# EPS_Flatsat_Module.net
KiCad netlist of a schematic drawn in EAGLE
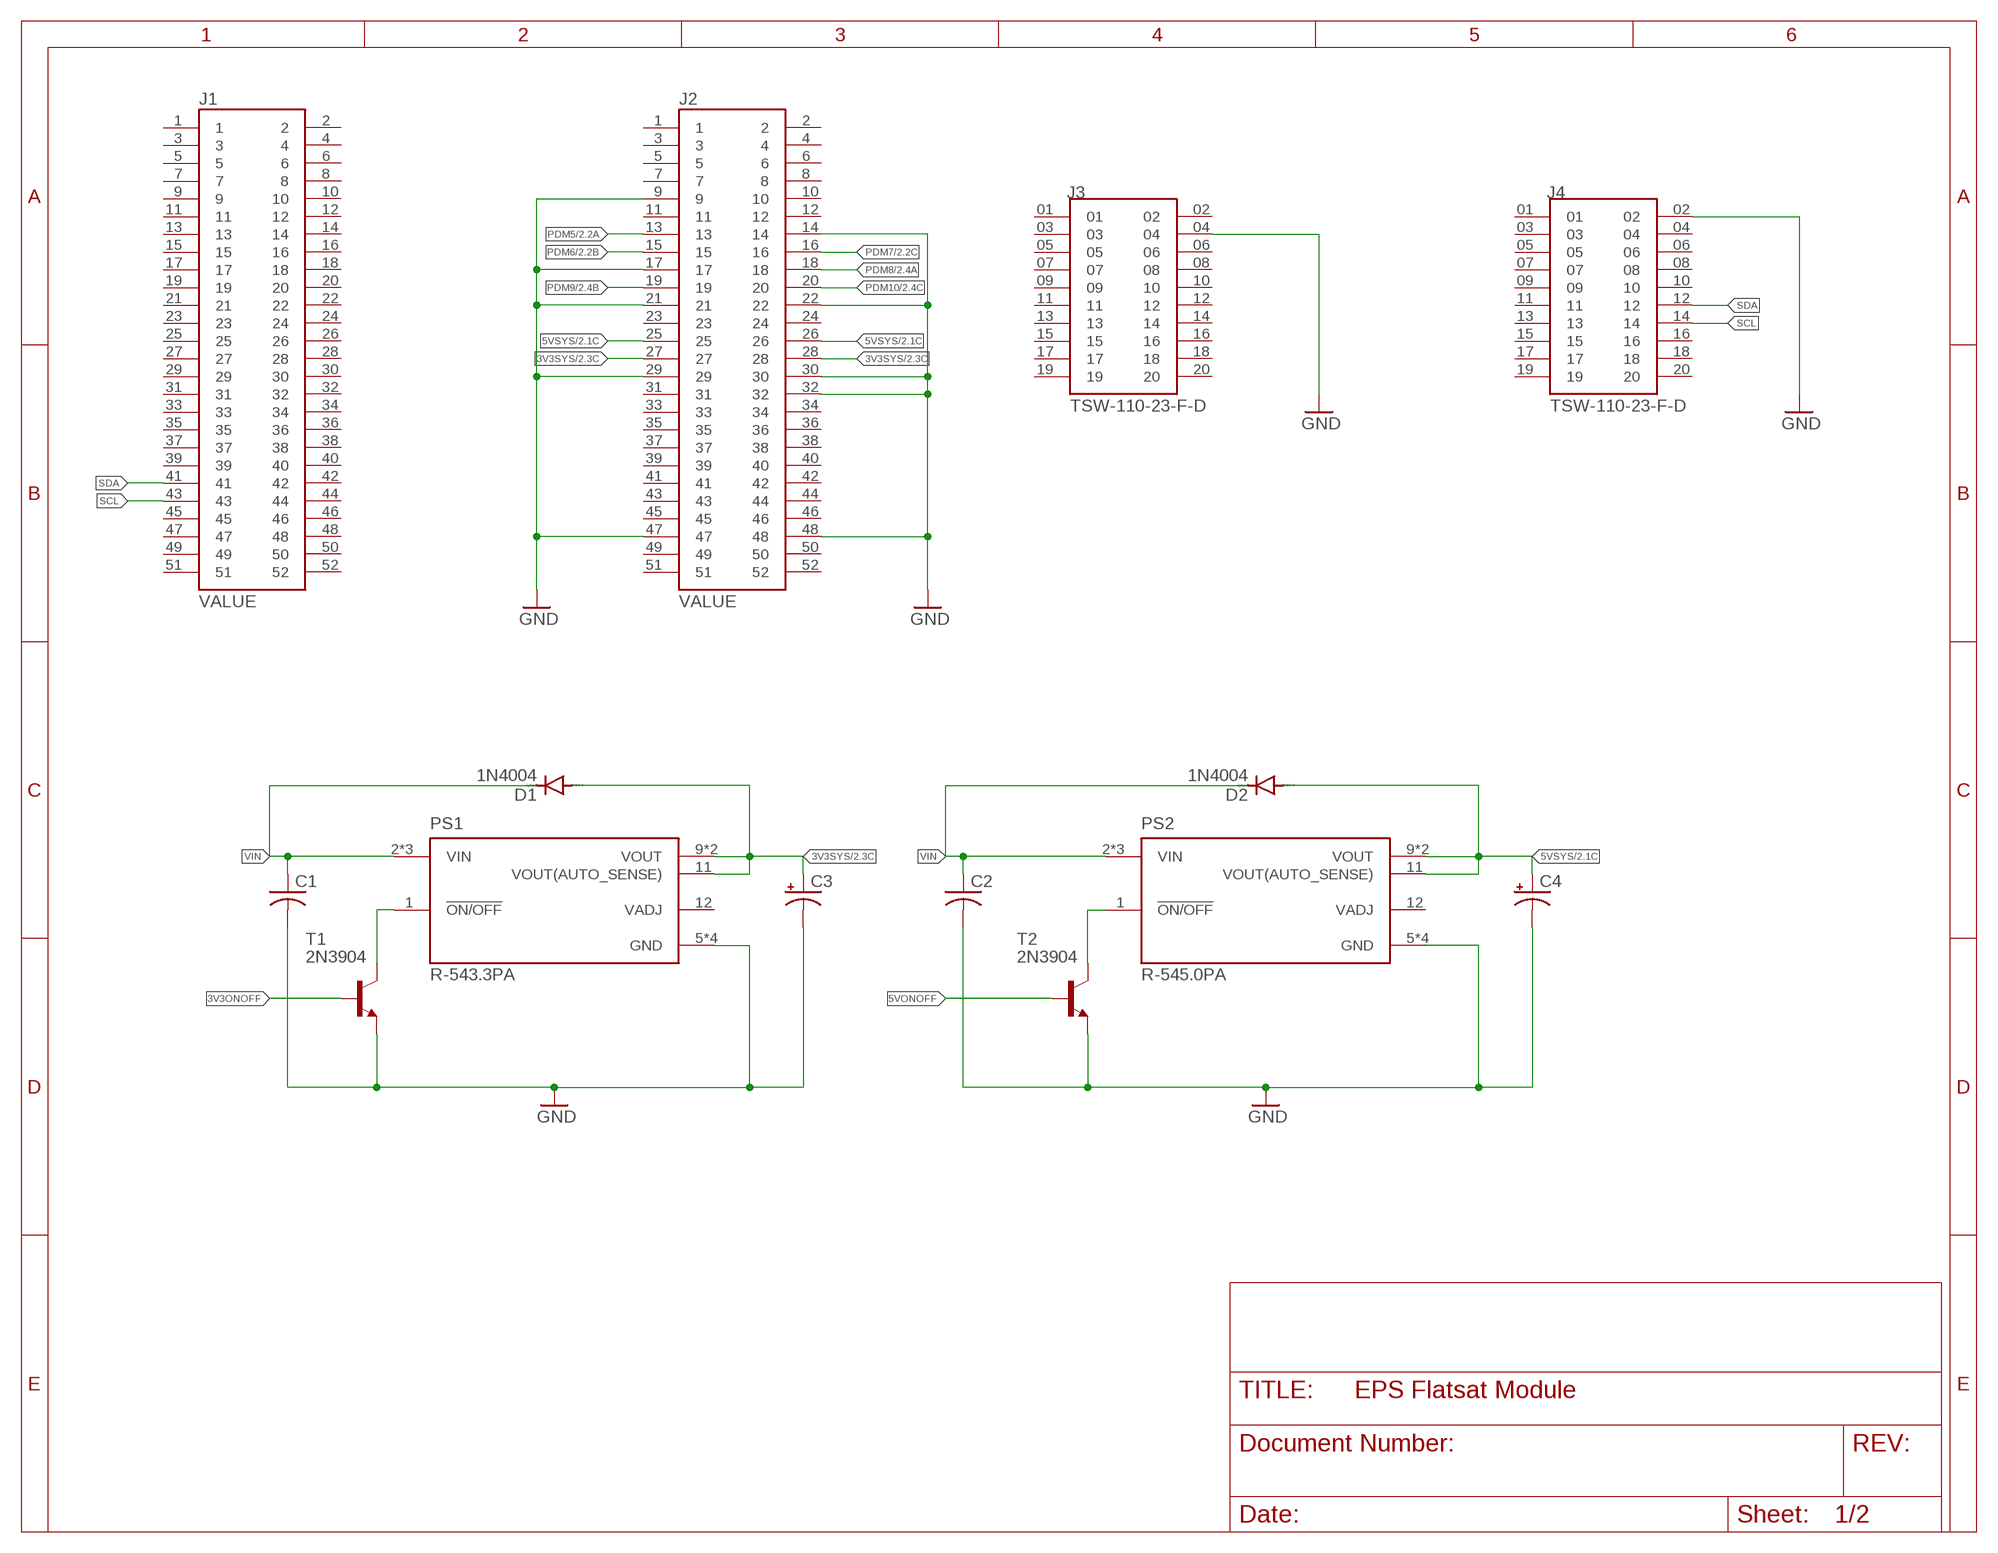
[diagram p0: schematic, sheet 1]
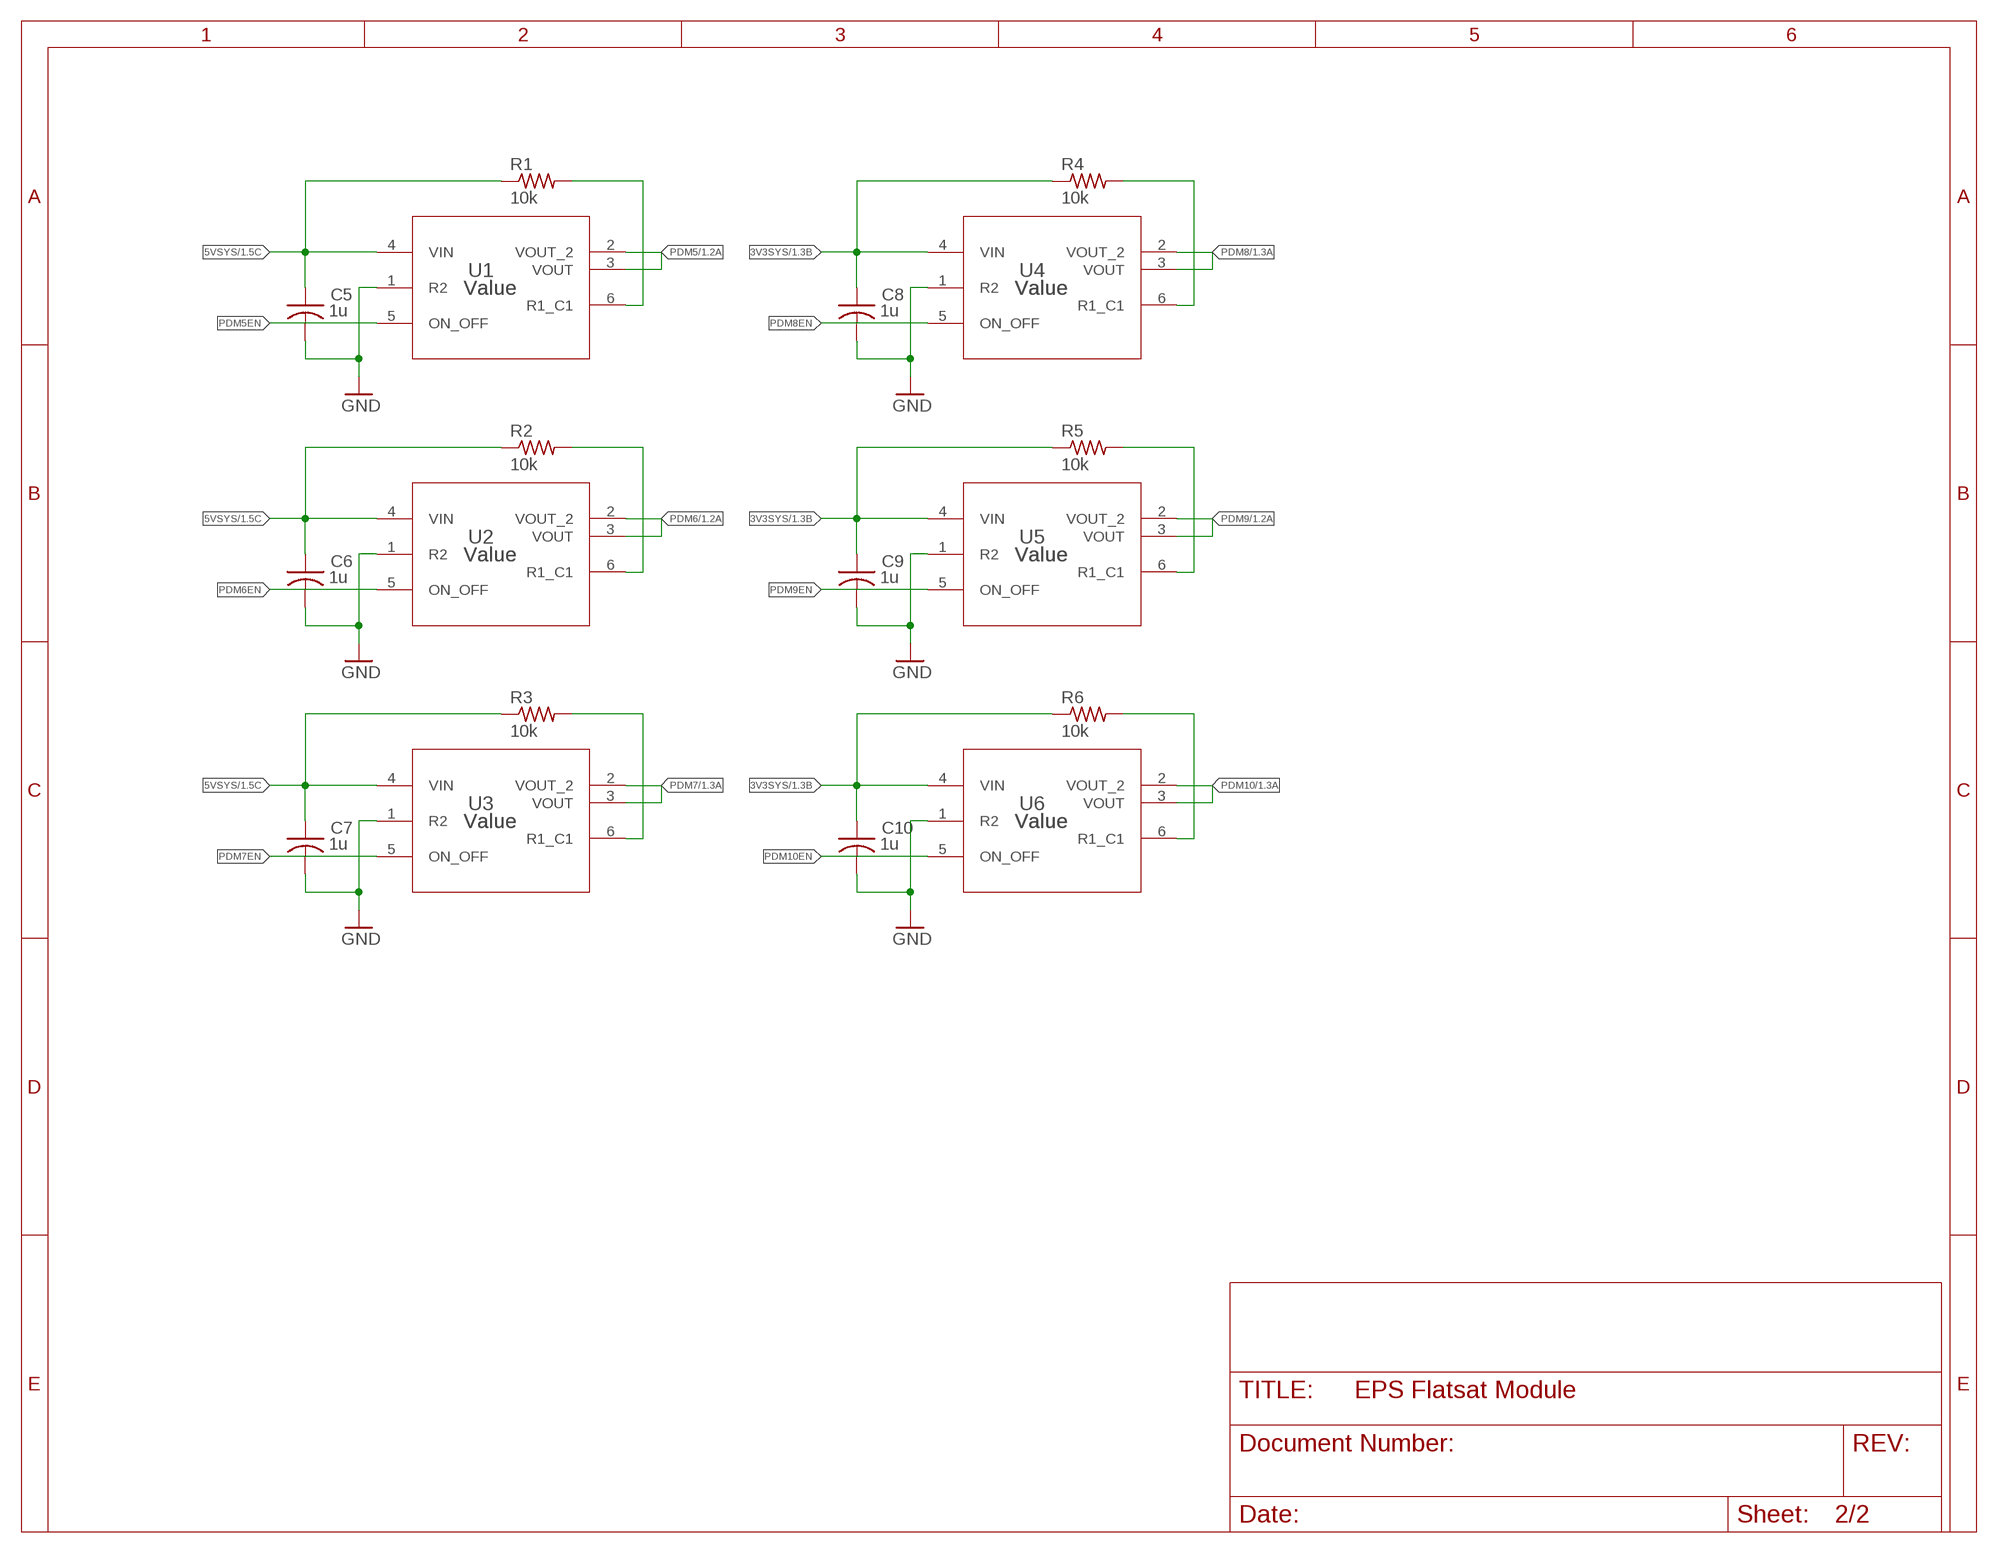
[diagram p1: schematic, sheet 2]

(export (version "E")
  (design (tool "Eeschema 10.0.6"))
  (components
    (comp (ref "C5")
      (value "1u")
      (footprint "eagle-import:C0805")
      (libsource (lib "eagle-import") (part "C-USC0805"))
    )
    (comp (ref "C6")
      (value "1u")
      (footprint "eagle-import:C0805")
      (libsource (lib "eagle-import") (part "C-USC0805"))
    )
    (comp (ref "C7")
      (value "1u")
      (footprint "eagle-import:C0805")
      (libsource (lib "eagle-import") (part "C-USC0805"))
    )
    (comp (ref "C8")
      (value "1u")
      (footprint "eagle-import:C0805")
      (libsource (lib "eagle-import") (part "C-USC0805"))
    )
    (comp (ref "C9")
      (value "1u")
      (footprint "eagle-import:C0805")
      (libsource (lib "eagle-import") (part "C-USC0805"))
    )
    (comp (ref "C10")
      (value "1u")
      (footprint "eagle-import:C0805")
      (libsource (lib "eagle-import") (part "C-USC0805"))
    )
    (comp (ref "R1")
      (value "10k")
      (footprint "eagle-import:R0805")
      (libsource (lib "eagle-import") (part "R-US_R0805"))
    )
    (comp (ref "R2")
      (value "10k")
      (footprint "eagle-import:R0805")
      (libsource (lib "eagle-import") (part "R-US_R0805"))
    )
    (comp (ref "R3")
      (value "10k")
      (footprint "eagle-import:R0805")
      (libsource (lib "eagle-import") (part "R-US_R0805"))
    )
    (comp (ref "R4")
      (value "10k")
      (footprint "eagle-import:R0805")
      (libsource (lib "eagle-import") (part "R-US_R0805"))
    )
    (comp (ref "R5")
      (value "10k")
      (footprint "eagle-import:R0805")
      (libsource (lib "eagle-import") (part "R-US_R0805"))
    )
    (comp (ref "R6")
      (value "10k")
      (footprint "eagle-import:R0805")
      (libsource (lib "eagle-import") (part "R-US_R0805"))
    )
    (comp (ref "U1")
      (value "Value")
      (footprint "eagle-import:DDC0006A_N")
      (fields (field (name "MANUFACTURER") "Texas Instruments") (field (name "PARTNUMBER") "TPS27081ADDCR"))
      (libsource (lib "eagle-import") (part "TPS27081ADDCR"))
    )
    (comp (ref "U2")
      (value "Value")
      (footprint "eagle-import:DDC0006A_N")
      (fields (field (name "MANUFACTURER") "Texas Instruments") (field (name "PARTNUMBER") "TPS27081ADDCR"))
      (libsource (lib "eagle-import") (part "TPS27081ADDCR"))
    )
    (comp (ref "U3")
      (value "Value")
      (footprint "eagle-import:DDC0006A_N")
      (fields (field (name "MANUFACTURER") "Texas Instruments") (field (name "PARTNUMBER") "TPS27081ADDCR"))
      (libsource (lib "eagle-import") (part "TPS27081ADDCR"))
    )
    (comp (ref "U4")
      (value "Value")
      (footprint "eagle-import:DDC0006A_N")
      (fields (field (name "MANUFACTURER") "Texas Instruments") (field (name "PARTNUMBER") "TPS27081ADDCR"))
      (libsource (lib "eagle-import") (part "TPS27081ADDCR"))
    )
    (comp (ref "U5")
      (value "Value")
      (footprint "eagle-import:DDC0006A_N")
      (fields (field (name "MANUFACTURER") "Texas Instruments") (field (name "PARTNUMBER") "TPS27081ADDCR"))
      (libsource (lib "eagle-import") (part "TPS27081ADDCR"))
    )
    (comp (ref "U6")
      (value "Value")
      (footprint "eagle-import:DDC0006A_N")
      (fields (field (name "MANUFACTURER") "Texas Instruments") (field (name "PARTNUMBER") "TPS27081ADDCR"))
      (libsource (lib "eagle-import") (part "TPS27081ADDCR"))
    )
    (comp (ref "C1")
      (value "C-USC0805")
      (footprint "eagle-import:C0805")
      (libsource (lib "eagle-import") (part "C-USC0805"))
    )
    (comp (ref "C2")
      (value "C-USC0805")
      (footprint "eagle-import:C0805")
      (libsource (lib "eagle-import") (part "C-USC0805"))
    )
    (comp (ref "C3")
      (value "CPOL-USE2.5-6")
      (footprint "eagle-import:E2,5-6")
      (libsource (lib "eagle-import") (part "CPOL-USE2.5-6"))
    )
    (comp (ref "C4")
      (value "CPOL-USE2.5-6")
      (footprint "eagle-import:E2,5-6")
      (libsource (lib "eagle-import") (part "CPOL-USE2.5-6"))
    )
    (comp (ref "D1")
      (value "1N4004")
      (footprint "eagle-import:DO41-10")
      (libsource (lib "eagle-import") (part "1N4004"))
    )
    (comp (ref "D2")
      (value "1N4004")
      (footprint "eagle-import:DO41-10")
      (libsource (lib "eagle-import") (part "1N4004"))
    )
    (comp (ref "J1")
      (value "ESQ-126-39-G-D")
      (footprint "eagle-import:SAMTEC_ESQ-126-39-G-D")
      (fields (field (name "DIGI-KEY_PART_NUMBER") "SAM10462-ND") (field (name "MF") "Samtec"))
      (libsource (lib "eagle-import") (part "ESQ-126-39-G-D"))
    )
    (comp (ref "J2")
      (value "ESQ-126-39-G-D")
      (footprint "eagle-import:SAMTEC_ESQ-126-39-G-D")
      (fields (field (name "DIGI-KEY_PART_NUMBER") "SAM10462-ND") (field (name "MF") "Samtec"))
      (libsource (lib "eagle-import") (part "ESQ-126-39-G-D"))
    )
    (comp (ref "J3")
      (value "TSW-110-23-F-D")
      (footprint "eagle-import:SAMTEC_TSW-110-23-F-D")
      (fields (field (name "MANUFACTURER") "Samtec"))
      (libsource (lib "eagle-import") (part "TSW-110-23-F-D"))
    )
    (comp (ref "J4")
      (value "TSW-110-23-F-D")
      (footprint "eagle-import:SAMTEC_TSW-110-23-F-D")
      (fields (field (name "MANUFACTURER") "Samtec"))
      (libsource (lib "eagle-import") (part "TSW-110-23-F-D"))
    )
    (comp (ref "PS1")
      (value "R-543.3PA")
      (footprint "eagle-import:CONV_R-543.3PA")
      (fields (field (name "DIGI-KEY_PART_NUMBER") "945-1599-5-ND") (field (name "MF") "Recom Power"))
      (libsource (lib "eagle-import") (part "R-543.3PA"))
    )
    (comp (ref "PS2")
      (value "R-545.0PA")
      (footprint "eagle-import:CONV_R-545.0PA")
      (fields (field (name "DIGI-KEY_PART_NUMBER") "R-545.0PA-ND") (field (name "MF") "Recom Power"))
      (libsource (lib "eagle-import") (part "R-545.0PA"))
    )
    (comp (ref "T1")
      (value "2N3904")
      (footprint "eagle-import:TO92")
      (libsource (lib "eagle-import") (part "2N3904"))
    )
    (comp (ref "T2")
      (value "2N3904")
      (footprint "eagle-import:TO92")
      (libsource (lib "eagle-import") (part "2N3904"))
    )
  )
  (nets
    (net (code "1") (name "3V3ONOFF") (class "Default")
      (node (ref "T1") (pin "2") (pinfunction "B_2") (pintype "passive"))
    )
    (net (code "2") (name "3V3SYS") (class "Default")
      (node (ref "C10") (pin "1") (pinfunction "1_1") (pintype "passive"))
      (node (ref "C3") (pin "+") (pinfunction "+_+") (pintype "passive"))
      (node (ref "C8") (pin "1") (pinfunction "1_1") (pintype "passive"))
      (node (ref "C9") (pin "1") (pinfunction "1_1") (pintype "passive"))
      (node (ref "D1") (pin "A") (pinfunction "A_A") (pintype "passive"))
      (node (ref "J2") (pin "27") (pinfunction "27_27") (pintype "passive"))
      (node (ref "J2") (pin "28") (pinfunction "28_28") (pintype "passive"))
      (node (ref "PS1") (pin "10") (pinfunction "VOUT_10") (pintype "output"))
      (node (ref "PS1") (pin "11") (pinfunction "VOUT(AUTO_SENSE)_11") (pintype "output"))
      (node (ref "PS1") (pin "9") (pinfunction "VOUT_9") (pintype "output"))
      (node (ref "R4") (pin "1") (pinfunction "1_1") (pintype "passive"))
      (node (ref "R5") (pin "1") (pinfunction "1_1") (pintype "passive"))
      (node (ref "R6") (pin "1") (pinfunction "1_1") (pintype "passive"))
      (node (ref "U4") (pin "4") (pinfunction "VIN_4") (pintype "power_in"))
      (node (ref "U5") (pin "4") (pinfunction "VIN_4") (pintype "power_in"))
      (node (ref "U6") (pin "4") (pinfunction "VIN_4") (pintype "power_in"))
    )
    (net (code "3") (name "5VONOFF") (class "Default")
      (node (ref "T2") (pin "2") (pinfunction "B_2") (pintype "passive"))
    )
    (net (code "4") (name "5VSYS") (class "Default")
      (node (ref "C4") (pin "+") (pinfunction "+_+") (pintype "passive"))
      (node (ref "C5") (pin "1") (pinfunction "1_1") (pintype "passive"))
      (node (ref "C6") (pin "1") (pinfunction "1_1") (pintype "passive"))
      (node (ref "C7") (pin "1") (pinfunction "1_1") (pintype "passive"))
      (node (ref "D2") (pin "A") (pinfunction "A_A") (pintype "passive"))
      (node (ref "J2") (pin "25") (pinfunction "25_25") (pintype "passive"))
      (node (ref "J2") (pin "26") (pinfunction "26_26") (pintype "passive"))
      (node (ref "PS2") (pin "10") (pinfunction "VOUT_10") (pintype "output"))
      (node (ref "PS2") (pin "11") (pinfunction "VOUT(AUTO_SENSE)_11") (pintype "output"))
      (node (ref "PS2") (pin "9") (pinfunction "VOUT_9") (pintype "output"))
      (node (ref "R1") (pin "1") (pinfunction "1_1") (pintype "passive"))
      (node (ref "R2") (pin "1") (pinfunction "1_1") (pintype "passive"))
      (node (ref "R3") (pin "1") (pinfunction "1_1") (pintype "passive"))
      (node (ref "U1") (pin "4") (pinfunction "VIN_4") (pintype "power_in"))
      (node (ref "U2") (pin "4") (pinfunction "VIN_4") (pintype "power_in"))
      (node (ref "U3") (pin "4") (pinfunction "VIN_4") (pintype "power_in"))
    )
    (net (code "5") (name "GND") (class "Default")
      (node (ref "C1") (pin "2") (pinfunction "2_2") (pintype "passive"))
      (node (ref "C10") (pin "2") (pinfunction "2_2") (pintype "passive"))
      (node (ref "C2") (pin "2") (pinfunction "2_2") (pintype "passive"))
      (node (ref "C3") (pin "-") (pinfunction "-_-") (pintype "passive"))
      (node (ref "C4") (pin "-") (pinfunction "-_-") (pintype "passive"))
      (node (ref "C5") (pin "2") (pinfunction "2_2") (pintype "passive"))
      (node (ref "C6") (pin "2") (pinfunction "2_2") (pintype "passive"))
      (node (ref "C7") (pin "2") (pinfunction "2_2") (pintype "passive"))
      (node (ref "C8") (pin "2") (pinfunction "2_2") (pintype "passive"))
      (node (ref "C9") (pin "2") (pinfunction "2_2") (pintype "passive"))
      (node (ref "J2") (pin "14") (pinfunction "14_14") (pintype "passive"))
      (node (ref "J2") (pin "17") (pinfunction "17_17") (pintype "passive"))
      (node (ref "J2") (pin "21") (pinfunction "21_21") (pintype "passive"))
      (node (ref "J2") (pin "22") (pinfunction "22_22") (pintype "passive"))
      (node (ref "J2") (pin "29") (pinfunction "29_29") (pintype "passive"))
      (node (ref "J2") (pin "30") (pinfunction "30_30") (pintype "passive"))
      (node (ref "J2") (pin "32") (pinfunction "32_32") (pintype "passive"))
      (node (ref "J2") (pin "47") (pinfunction "47_47") (pintype "passive"))
      (node (ref "J2") (pin "48") (pinfunction "48_48") (pintype "passive"))
      (node (ref "J2") (pin "9") (pinfunction "9_9") (pintype "passive"))
      (node (ref "J3") (pin "04") (pinfunction "04_04") (pintype "passive"))
      (node (ref "J4") (pin "02") (pinfunction "02_02") (pintype "passive"))
      (node (ref "PS1") (pin "5") (pinfunction "GND_5") (pintype "power_in"))
      (node (ref "PS1") (pin "6") (pinfunction "GND_6") (pintype "power_in"))
      (node (ref "PS1") (pin "7") (pinfunction "GND_7") (pintype "power_in"))
      (node (ref "PS1") (pin "8") (pinfunction "GND_8") (pintype "power_in"))
      (node (ref "PS2") (pin "5") (pinfunction "GND_5") (pintype "power_in"))
      (node (ref "PS2") (pin "6") (pinfunction "GND_6") (pintype "power_in"))
      (node (ref "PS2") (pin "7") (pinfunction "GND_7") (pintype "power_in"))
      (node (ref "PS2") (pin "8") (pinfunction "GND_8") (pintype "power_in"))
      (node (ref "T1") (pin "3") (pinfunction "E_3") (pintype "passive"))
      (node (ref "T2") (pin "3") (pinfunction "E_3") (pintype "passive"))
      (node (ref "U1") (pin "1") (pinfunction "R2_1") (pintype "input"))
      (node (ref "U2") (pin "1") (pinfunction "R2_1") (pintype "input"))
      (node (ref "U3") (pin "1") (pinfunction "R2_1") (pintype "input"))
      (node (ref "U4") (pin "1") (pinfunction "R2_1") (pintype "input"))
      (node (ref "U5") (pin "1") (pinfunction "R2_1") (pintype "input"))
      (node (ref "U6") (pin "1") (pinfunction "R2_1") (pintype "input"))
    )
    (net (code "6") (name "Net-(PS1-~{ON{slash}OFF})") (class "Default")
      (node (ref "PS1") (pin "1") (pinfunction "~{ON/OFF}_1") (pintype "input"))
      (node (ref "T1") (pin "1") (pinfunction "C_1") (pintype "passive"))
    )
    (net (code "7") (name "Net-(PS2-~{ON{slash}OFF})") (class "Default")
      (node (ref "PS2") (pin "1") (pinfunction "~{ON/OFF}_1") (pintype "input"))
      (node (ref "T2") (pin "1") (pinfunction "C_1") (pintype "passive"))
    )
    (net (code "8") (name "Net-(U1-R1_C1)") (class "Default")
      (node (ref "R1") (pin "2") (pinfunction "2_2") (pintype "passive"))
      (node (ref "U1") (pin "6") (pinfunction "R1_C1_6") (pintype "input"))
    )
    (net (code "9") (name "Net-(U2-R1_C1)") (class "Default")
      (node (ref "R2") (pin "2") (pinfunction "2_2") (pintype "passive"))
      (node (ref "U2") (pin "6") (pinfunction "R1_C1_6") (pintype "input"))
    )
    (net (code "10") (name "Net-(U3-R1_C1)") (class "Default")
      (node (ref "R3") (pin "2") (pinfunction "2_2") (pintype "passive"))
      (node (ref "U3") (pin "6") (pinfunction "R1_C1_6") (pintype "input"))
    )
    (net (code "11") (name "Net-(U4-R1_C1)") (class "Default")
      (node (ref "R4") (pin "2") (pinfunction "2_2") (pintype "passive"))
      (node (ref "U4") (pin "6") (pinfunction "R1_C1_6") (pintype "input"))
    )
    (net (code "12") (name "Net-(U5-R1_C1)") (class "Default")
      (node (ref "R5") (pin "2") (pinfunction "2_2") (pintype "passive"))
      (node (ref "U5") (pin "6") (pinfunction "R1_C1_6") (pintype "input"))
    )
    (net (code "13") (name "Net-(U6-R1_C1)") (class "Default")
      (node (ref "R6") (pin "2") (pinfunction "2_2") (pintype "passive"))
      (node (ref "U6") (pin "6") (pinfunction "R1_C1_6") (pintype "input"))
    )
    (net (code "14") (name "PDM5") (class "Default")
      (node (ref "J2") (pin "13") (pinfunction "13_13") (pintype "passive"))
      (node (ref "U1") (pin "2") (pinfunction "VOUT_2_2") (pintype "power_in"))
      (node (ref "U1") (pin "3") (pinfunction "VOUT_3") (pintype "power_in"))
    )
    (net (code "15") (name "PDM5EN") (class "Default")
      (node (ref "U1") (pin "5") (pinfunction "ON_OFF_5") (pintype "input"))
    )
    (net (code "16") (name "PDM6") (class "Default")
      (node (ref "J2") (pin "15") (pinfunction "15_15") (pintype "passive"))
      (node (ref "U2") (pin "2") (pinfunction "VOUT_2_2") (pintype "power_in"))
      (node (ref "U2") (pin "3") (pinfunction "VOUT_3") (pintype "power_in"))
    )
    (net (code "17") (name "PDM6EN") (class "Default")
      (node (ref "U2") (pin "5") (pinfunction "ON_OFF_5") (pintype "input"))
    )
    (net (code "18") (name "PDM7") (class "Default")
      (node (ref "J2") (pin "16") (pinfunction "16_16") (pintype "passive"))
      (node (ref "U3") (pin "2") (pinfunction "VOUT_2_2") (pintype "power_in"))
      (node (ref "U3") (pin "3") (pinfunction "VOUT_3") (pintype "power_in"))
    )
    (net (code "19") (name "PDM7EN") (class "Default")
      (node (ref "U3") (pin "5") (pinfunction "ON_OFF_5") (pintype "input"))
    )
    (net (code "20") (name "PDM8") (class "Default")
      (node (ref "J2") (pin "18") (pinfunction "18_18") (pintype "passive"))
      (node (ref "U4") (pin "2") (pinfunction "VOUT_2_2") (pintype "power_in"))
      (node (ref "U4") (pin "3") (pinfunction "VOUT_3") (pintype "power_in"))
    )
    (net (code "21") (name "PDM8EN") (class "Default")
      (node (ref "U4") (pin "5") (pinfunction "ON_OFF_5") (pintype "input"))
    )
    (net (code "22") (name "PDM9") (class "Default")
      (node (ref "J2") (pin "19") (pinfunction "19_19") (pintype "passive"))
      (node (ref "U5") (pin "2") (pinfunction "VOUT_2_2") (pintype "power_in"))
      (node (ref "U5") (pin "3") (pinfunction "VOUT_3") (pintype "power_in"))
    )
    (net (code "23") (name "PDM9EN") (class "Default")
      (node (ref "U5") (pin "5") (pinfunction "ON_OFF_5") (pintype "input"))
    )
    (net (code "24") (name "PDM10") (class "Default")
      (node (ref "J2") (pin "20") (pinfunction "20_20") (pintype "passive"))
      (node (ref "U6") (pin "2") (pinfunction "VOUT_2_2") (pintype "power_in"))
      (node (ref "U6") (pin "3") (pinfunction "VOUT_3") (pintype "power_in"))
    )
    (net (code "25") (name "PDM10EN") (class "Default")
      (node (ref "U6") (pin "5") (pinfunction "ON_OFF_5") (pintype "input"))
    )
    (net (code "26") (name "SCL") (class "Default")
      (node (ref "J1") (pin "43") (pinfunction "43_43") (pintype "passive"))
      (node (ref "J4") (pin "14") (pinfunction "14_14") (pintype "passive"))
    )
    (net (code "27") (name "SDA") (class "Default")
      (node (ref "J1") (pin "41") (pinfunction "41_41") (pintype "passive"))
      (node (ref "J4") (pin "12") (pinfunction "12_12") (pintype "passive"))
    )
    (net (code "28") (name "VIN") (class "Default")
      (node (ref "C1") (pin "1") (pinfunction "1_1") (pintype "passive"))
      (node (ref "C2") (pin "1") (pinfunction "1_1") (pintype "passive"))
      (node (ref "D1") (pin "C") (pinfunction "C_C") (pintype "passive"))
      (node (ref "D2") (pin "C") (pinfunction "C_C") (pintype "passive"))
      (node (ref "PS1") (pin "2") (pinfunction "VIN_2") (pintype "input"))
      (node (ref "PS1") (pin "3") (pinfunction "VIN_3") (pintype "input"))
      (node (ref "PS1") (pin "4") (pinfunction "VIN_4") (pintype "input"))
      (node (ref "PS2") (pin "2") (pinfunction "VIN_2") (pintype "input"))
      (node (ref "PS2") (pin "3") (pinfunction "VIN_3") (pintype "input"))
      (node (ref "PS2") (pin "4") (pinfunction "VIN_4") (pintype "input"))
    )
    (net (code "29") (name "unconnected-(J1-Pad1)") (class "Default")
      (node (ref "J1") (pin "1") (pinfunction "1_1") (pintype "passive"))
    )
    (net (code "30") (name "unconnected-(J1-Pad2)") (class "Default")
      (node (ref "J1") (pin "2") (pinfunction "2_2") (pintype "passive"))
    )
    (net (code "31") (name "unconnected-(J1-Pad3)") (class "Default")
      (node (ref "J1") (pin "3") (pinfunction "3_3") (pintype "passive"))
    )
    (net (code "32") (name "unconnected-(J1-Pad4)") (class "Default")
      (node (ref "J1") (pin "4") (pinfunction "4_4") (pintype "passive"))
    )
    (net (code "33") (name "unconnected-(J1-Pad5)") (class "Default")
      (node (ref "J1") (pin "5") (pinfunction "5_5") (pintype "passive"))
    )
    (net (code "34") (name "unconnected-(J1-Pad6)") (class "Default")
      (node (ref "J1") (pin "6") (pinfunction "6_6") (pintype "passive"))
    )
    (net (code "35") (name "unconnected-(J1-Pad7)") (class "Default")
      (node (ref "J1") (pin "7") (pinfunction "7_7") (pintype "passive"))
    )
    (net (code "36") (name "unconnected-(J1-Pad8)") (class "Default")
      (node (ref "J1") (pin "8") (pinfunction "8_8") (pintype "passive"))
    )
    (net (code "37") (name "unconnected-(J1-Pad9)") (class "Default")
      (node (ref "J1") (pin "9") (pinfunction "9_9") (pintype "passive"))
    )
    (net (code "38") (name "unconnected-(J1-Pad10)") (class "Default")
      (node (ref "J1") (pin "10") (pinfunction "10_10") (pintype "passive"))
    )
    (net (code "39") (name "unconnected-(J1-Pad11)") (class "Default")
      (node (ref "J1") (pin "11") (pinfunction "11_11") (pintype "passive"))
    )
    (net (code "40") (name "unconnected-(J1-Pad12)") (class "Default")
      (node (ref "J1") (pin "12") (pinfunction "12_12") (pintype "passive"))
    )
    (net (code "41") (name "unconnected-(J1-Pad13)") (class "Default")
      (node (ref "J1") (pin "13") (pinfunction "13_13") (pintype "passive"))
    )
    (net (code "42") (name "unconnected-(J1-Pad14)") (class "Default")
      (node (ref "J1") (pin "14") (pinfunction "14_14") (pintype "passive"))
    )
    (net (code "43") (name "unconnected-(J1-Pad15)") (class "Default")
      (node (ref "J1") (pin "15") (pinfunction "15_15") (pintype "passive"))
    )
    (net (code "44") (name "unconnected-(J1-Pad16)") (class "Default")
      (node (ref "J1") (pin "16") (pinfunction "16_16") (pintype "passive"))
    )
    (net (code "45") (name "unconnected-(J1-Pad17)") (class "Default")
      (node (ref "J1") (pin "17") (pinfunction "17_17") (pintype "passive"))
    )
    (net (code "46") (name "unconnected-(J1-Pad18)") (class "Default")
      (node (ref "J1") (pin "18") (pinfunction "18_18") (pintype "passive"))
    )
    (net (code "47") (name "unconnected-(J1-Pad19)") (class "Default")
      (node (ref "J1") (pin "19") (pinfunction "19_19") (pintype "passive"))
    )
    (net (code "48") (name "unconnected-(J1-Pad20)") (class "Default")
      (node (ref "J1") (pin "20") (pinfunction "20_20") (pintype "passive"))
    )
    (net (code "49") (name "unconnected-(J1-Pad21)") (class "Default")
      (node (ref "J1") (pin "21") (pinfunction "21_21") (pintype "passive"))
    )
    (net (code "50") (name "unconnected-(J1-Pad22)") (class "Default")
      (node (ref "J1") (pin "22") (pinfunction "22_22") (pintype "passive"))
    )
    (net (code "51") (name "unconnected-(J1-Pad23)") (class "Default")
      (node (ref "J1") (pin "23") (pinfunction "23_23") (pintype "passive"))
    )
    (net (code "52") (name "unconnected-(J1-Pad24)") (class "Default")
      (node (ref "J1") (pin "24") (pinfunction "24_24") (pintype "passive"))
    )
    (net (code "53") (name "unconnected-(J1-Pad25)") (class "Default")
      (node (ref "J1") (pin "25") (pinfunction "25_25") (pintype "passive"))
    )
    (net (code "54") (name "unconnected-(J1-Pad26)") (class "Default")
      (node (ref "J1") (pin "26") (pinfunction "26_26") (pintype "passive"))
    )
    (net (code "55") (name "unconnected-(J1-Pad27)") (class "Default")
      (node (ref "J1") (pin "27") (pinfunction "27_27") (pintype "passive"))
    )
    (net (code "56") (name "unconnected-(J1-Pad28)") (class "Default")
      (node (ref "J1") (pin "28") (pinfunction "28_28") (pintype "passive"))
    )
    (net (code "57") (name "unconnected-(J1-Pad29)") (class "Default")
      (node (ref "J1") (pin "29") (pinfunction "29_29") (pintype "passive"))
    )
    (net (code "58") (name "unconnected-(J1-Pad30)") (class "Default")
      (node (ref "J1") (pin "30") (pinfunction "30_30") (pintype "passive"))
    )
    (net (code "59") (name "unconnected-(J1-Pad31)") (class "Default")
      (node (ref "J1") (pin "31") (pinfunction "31_31") (pintype "passive"))
    )
    (net (code "60") (name "unconnected-(J1-Pad32)") (class "Default")
      (node (ref "J1") (pin "32") (pinfunction "32_32") (pintype "passive"))
    )
    (net (code "61") (name "unconnected-(J1-Pad33)") (class "Default")
      (node (ref "J1") (pin "33") (pinfunction "33_33") (pintype "passive"))
    )
    (net (code "62") (name "unconnected-(J1-Pad34)") (class "Default")
      (node (ref "J1") (pin "34") (pinfunction "34_34") (pintype "passive"))
    )
    (net (code "63") (name "unconnected-(J1-Pad35)") (class "Default")
      (node (ref "J1") (pin "35") (pinfunction "35_35") (pintype "passive"))
    )
    (net (code "64") (name "unconnected-(J1-Pad36)") (class "Default")
      (node (ref "J1") (pin "36") (pinfunction "36_36") (pintype "passive"))
    )
    (net (code "65") (name "unconnected-(J1-Pad37)") (class "Default")
      (node (ref "J1") (pin "37") (pinfunction "37_37") (pintype "passive"))
    )
    (net (code "66") (name "unconnected-(J1-Pad38)") (class "Default")
      (node (ref "J1") (pin "38") (pinfunction "38_38") (pintype "passive"))
    )
    (net (code "67") (name "unconnected-(J1-Pad39)") (class "Default")
      (node (ref "J1") (pin "39") (pinfunction "39_39") (pintype "passive"))
    )
    (net (code "68") (name "unconnected-(J1-Pad40)") (class "Default")
      (node (ref "J1") (pin "40") (pinfunction "40_40") (pintype "passive"))
    )
    (net (code "69") (name "unconnected-(J1-Pad42)") (class "Default")
      (node (ref "J1") (pin "42") (pinfunction "42_42") (pintype "passive"))
    )
    (net (code "70") (name "unconnected-(J1-Pad44)") (class "Default")
      (node (ref "J1") (pin "44") (pinfunction "44_44") (pintype "passive"))
    )
    (net (code "71") (name "unconnected-(J1-Pad45)") (class "Default")
      (node (ref "J1") (pin "45") (pinfunction "45_45") (pintype "passive"))
    )
    (net (code "72") (name "unconnected-(J1-Pad46)") (class "Default")
      (node (ref "J1") (pin "46") (pinfunction "46_46") (pintype "passive"))
    )
    (net (code "73") (name "unconnected-(J1-Pad47)") (class "Default")
      (node (ref "J1") (pin "47") (pinfunction "47_47") (pintype "passive"))
    )
    (net (code "74") (name "unconnected-(J1-Pad48)") (class "Default")
      (node (ref "J1") (pin "48") (pinfunction "48_48") (pintype "passive"))
    )
    (net (code "75") (name "unconnected-(J1-Pad49)") (class "Default")
      (node (ref "J1") (pin "49") (pinfunction "49_49") (pintype "passive"))
    )
    (net (code "76") (name "unconnected-(J1-Pad50)") (class "Default")
      (node (ref "J1") (pin "50") (pinfunction "50_50") (pintype "passive"))
    )
    (net (code "77") (name "unconnected-(J1-Pad51)") (class "Default")
      (node (ref "J1") (pin "51") (pinfunction "51_51") (pintype "passive"))
    )
    (net (code "78") (name "unconnected-(J1-Pad52)") (class "Default")
      (node (ref "J1") (pin "52") (pinfunction "52_52") (pintype "passive"))
    )
    (net (code "79") (name "unconnected-(J2-Pad1)") (class "Default")
      (node (ref "J2") (pin "1") (pinfunction "1_1") (pintype "passive"))
    )
    (net (code "80") (name "unconnected-(J2-Pad2)") (class "Default")
      (node (ref "J2") (pin "2") (pinfunction "2_2") (pintype "passive"))
    )
    (net (code "81") (name "unconnected-(J2-Pad3)") (class "Default")
      (node (ref "J2") (pin "3") (pinfunction "3_3") (pintype "passive"))
    )
    (net (code "82") (name "unconnected-(J2-Pad4)") (class "Default")
      (node (ref "J2") (pin "4") (pinfunction "4_4") (pintype "passive"))
    )
    (net (code "83") (name "unconnected-(J2-Pad5)") (class "Default")
      (node (ref "J2") (pin "5") (pinfunction "5_5") (pintype "passive"))
    )
    (net (code "84") (name "unconnected-(J2-Pad6)") (class "Default")
      (node (ref "J2") (pin "6") (pinfunction "6_6") (pintype "passive"))
    )
    (net (code "85") (name "unconnected-(J2-Pad7)") (class "Default")
      (node (ref "J2") (pin "7") (pinfunction "7_7") (pintype "passive"))
    )
    (net (code "86") (name "unconnected-(J2-Pad8)") (class "Default")
      (node (ref "J2") (pin "8") (pinfunction "8_8") (pintype "passive"))
    )
    (net (code "87") (name "unconnected-(J2-Pad10)") (class "Default")
      (node (ref "J2") (pin "10") (pinfunction "10_10") (pintype "passive"))
    )
    (net (code "88") (name "unconnected-(J2-Pad11)") (class "Default")
      (node (ref "J2") (pin "11") (pinfunction "11_11") (pintype "passive"))
    )
    (net (code "89") (name "unconnected-(J2-Pad12)") (class "Default")
      (node (ref "J2") (pin "12") (pinfunction "12_12") (pintype "passive"))
    )
    (net (code "90") (name "unconnected-(J2-Pad23)") (class "Default")
      (node (ref "J2") (pin "23") (pinfunction "23_23") (pintype "passive"))
    )
    (net (code "91") (name "unconnected-(J2-Pad24)") (class "Default")
      (node (ref "J2") (pin "24") (pinfunction "24_24") (pintype "passive"))
    )
    (net (code "92") (name "unconnected-(J2-Pad31)") (class "Default")
      (node (ref "J2") (pin "31") (pinfunction "31_31") (pintype "passive"))
    )
    (net (code "93") (name "unconnected-(J2-Pad33)") (class "Default")
      (node (ref "J2") (pin "33") (pinfunction "33_33") (pintype "passive"))
    )
    (net (code "94") (name "unconnected-(J2-Pad34)") (class "Default")
      (node (ref "J2") (pin "34") (pinfunction "34_34") (pintype "passive"))
    )
    (net (code "95") (name "unconnected-(J2-Pad35)") (class "Default")
      (node (ref "J2") (pin "35") (pinfunction "35_35") (pintype "passive"))
    )
    (net (code "96") (name "unconnected-(J2-Pad36)") (class "Default")
      (node (ref "J2") (pin "36") (pinfunction "36_36") (pintype "passive"))
    )
    (net (code "97") (name "unconnected-(J2-Pad37)") (class "Default")
      (node (ref "J2") (pin "37") (pinfunction "37_37") (pintype "passive"))
    )
    (net (code "98") (name "unconnected-(J2-Pad38)") (class "Default")
      (node (ref "J2") (pin "38") (pinfunction "38_38") (pintype "passive"))
    )
    (net (code "99") (name "unconnected-(J2-Pad39)") (class "Default")
      (node (ref "J2") (pin "39") (pinfunction "39_39") (pintype "passive"))
    )
    (net (code "100") (name "unconnected-(J2-Pad40)") (class "Default")
      (node (ref "J2") (pin "40") (pinfunction "40_40") (pintype "passive"))
    )
    (net (code "101") (name "unconnected-(J2-Pad41)") (class "Default")
      (node (ref "J2") (pin "41") (pinfunction "41_41") (pintype "passive"))
    )
    (net (code "102") (name "unconnected-(J2-Pad42)") (class "Default")
      (node (ref "J2") (pin "42") (pinfunction "42_42") (pintype "passive"))
    )
    (net (code "103") (name "unconnected-(J2-Pad43)") (class "Default")
      (node (ref "J2") (pin "43") (pinfunction "43_43") (pintype "passive"))
    )
    (net (code "104") (name "unconnected-(J2-Pad44)") (class "Default")
      (node (ref "J2") (pin "44") (pinfunction "44_44") (pintype "passive"))
    )
    (net (code "105") (name "unconnected-(J2-Pad45)") (class "Default")
      (node (ref "J2") (pin "45") (pinfunction "45_45") (pintype "passive"))
    )
    (net (code "106") (name "unconnected-(J2-Pad46)") (class "Default")
      (node (ref "J2") (pin "46") (pinfunction "46_46") (pintype "passive"))
    )
    (net (code "107") (name "unconnected-(J2-Pad49)") (class "Default")
      (node (ref "J2") (pin "49") (pinfunction "49_49") (pintype "passive"))
    )
    (net (code "108") (name "unconnected-(J2-Pad50)") (class "Default")
      (node (ref "J2") (pin "50") (pinfunction "50_50") (pintype "passive"))
    )
    (net (code "109") (name "unconnected-(J2-Pad51)") (class "Default")
      (node (ref "J2") (pin "51") (pinfunction "51_51") (pintype "passive"))
    )
    (net (code "110") (name "unconnected-(J2-Pad52)") (class "Default")
      (node (ref "J2") (pin "52") (pinfunction "52_52") (pintype "passive"))
    )
    (net (code "111") (name "unconnected-(J3-Pad01)") (class "Default")
      (node (ref "J3") (pin "01") (pinfunction "01_01") (pintype "passive"))
    )
    (net (code "112") (name "unconnected-(J3-Pad02)") (class "Default")
      (node (ref "J3") (pin "02") (pinfunction "02_02") (pintype "passive"))
    )
    (net (code "113") (name "unconnected-(J3-Pad03)") (class "Default")
      (node (ref "J3") (pin "03") (pinfunction "03_03") (pintype "passive"))
    )
    (net (code "114") (name "unconnected-(J3-Pad05)") (class "Default")
      (node (ref "J3") (pin "05") (pinfunction "05_05") (pintype "passive"))
    )
    (net (code "115") (name "unconnected-(J3-Pad06)") (class "Default")
      (node (ref "J3") (pin "06") (pinfunction "06_06") (pintype "passive"))
    )
    (net (code "116") (name "unconnected-(J3-Pad07)") (class "Default")
      (node (ref "J3") (pin "07") (pinfunction "07_07") (pintype "passive"))
    )
    (net (code "117") (name "unconnected-(J3-Pad08)") (class "Default")
      (node (ref "J3") (pin "08") (pinfunction "08_08") (pintype "passive"))
    )
    (net (code "118") (name "unconnected-(J3-Pad09)") (class "Default")
      (node (ref "J3") (pin "09") (pinfunction "09_09") (pintype "passive"))
    )
    (net (code "119") (name "unconnected-(J3-Pad10)") (class "Default")
      (node (ref "J3") (pin "10") (pinfunction "10_10") (pintype "passive"))
    )
    (net (code "120") (name "unconnected-(J3-Pad11)") (class "Default")
      (node (ref "J3") (pin "11") (pinfunction "11_11") (pintype "passive"))
    )
    (net (code "121") (name "unconnected-(J3-Pad12)") (class "Default")
      (node (ref "J3") (pin "12") (pinfunction "12_12") (pintype "passive"))
    )
    (net (code "122") (name "unconnected-(J3-Pad13)") (class "Default")
      (node (ref "J3") (pin "13") (pinfunction "13_13") (pintype "passive"))
    )
    (net (code "123") (name "unconnected-(J3-Pad14)") (class "Default")
      (node (ref "J3") (pin "14") (pinfunction "14_14") (pintype "passive"))
    )
    (net (code "124") (name "unconnected-(J3-Pad15)") (class "Default")
      (node (ref "J3") (pin "15") (pinfunction "15_15") (pintype "passive"))
    )
    (net (code "125") (name "unconnected-(J3-Pad16)") (class "Default")
      (node (ref "J3") (pin "16") (pinfunction "16_16") (pintype "passive"))
    )
    (net (code "126") (name "unconnected-(J3-Pad17)") (class "Default")
      (node (ref "J3") (pin "17") (pinfunction "17_17") (pintype "passive"))
    )
    (net (code "127") (name "unconnected-(J3-Pad18)") (class "Default")
      (node (ref "J3") (pin "18") (pinfunction "18_18") (pintype "passive"))
    )
    (net (code "128") (name "unconnected-(J3-Pad19)") (class "Default")
      (node (ref "J3") (pin "19") (pinfunction "19_19") (pintype "passive"))
    )
    (net (code "129") (name "unconnected-(J3-Pad20)") (class "Default")
      (node (ref "J3") (pin "20") (pinfunction "20_20") (pintype "passive"))
    )
    (net (code "130") (name "unconnected-(J4-Pad01)") (class "Default")
      (node (ref "J4") (pin "01") (pinfunction "01_01") (pintype "passive"))
    )
    (net (code "131") (name "unconnected-(J4-Pad03)") (class "Default")
      (node (ref "J4") (pin "03") (pinfunction "03_03") (pintype "passive"))
    )
    (net (code "132") (name "unconnected-(J4-Pad04)") (class "Default")
      (node (ref "J4") (pin "04") (pinfunction "04_04") (pintype "passive"))
    )
    (net (code "133") (name "unconnected-(J4-Pad05)") (class "Default")
      (node (ref "J4") (pin "05") (pinfunction "05_05") (pintype "passive"))
    )
    (net (code "134") (name "unconnected-(J4-Pad06)") (class "Default")
      (node (ref "J4") (pin "06") (pinfunction "06_06") (pintype "passive"))
    )
    (net (code "135") (name "unconnected-(J4-Pad07)") (class "Default")
      (node (ref "J4") (pin "07") (pinfunction "07_07") (pintype "passive"))
    )
    (net (code "136") (name "unconnected-(J4-Pad08)") (class "Default")
      (node (ref "J4") (pin "08") (pinfunction "08_08") (pintype "passive"))
    )
    (net (code "137") (name "unconnected-(J4-Pad09)") (class "Default")
      (node (ref "J4") (pin "09") (pinfunction "09_09") (pintype "passive"))
    )
    (net (code "138") (name "unconnected-(J4-Pad10)") (class "Default")
      (node (ref "J4") (pin "10") (pinfunction "10_10") (pintype "passive"))
    )
    (net (code "139") (name "unconnected-(J4-Pad11)") (class "Default")
      (node (ref "J4") (pin "11") (pinfunction "11_11") (pintype "passive"))
    )
    (net (code "140") (name "unconnected-(J4-Pad13)") (class "Default")
      (node (ref "J4") (pin "13") (pinfunction "13_13") (pintype "passive"))
    )
    (net (code "141") (name "unconnected-(J4-Pad15)") (class "Default")
      (node (ref "J4") (pin "15") (pinfunction "15_15") (pintype "passive"))
    )
    (net (code "142") (name "unconnected-(J4-Pad16)") (class "Default")
      (node (ref "J4") (pin "16") (pinfunction "16_16") (pintype "passive"))
    )
    (net (code "143") (name "unconnected-(J4-Pad17)") (class "Default")
      (node (ref "J4") (pin "17") (pinfunction "17_17") (pintype "passive"))
    )
    (net (code "144") (name "unconnected-(J4-Pad18)") (class "Default")
      (node (ref "J4") (pin "18") (pinfunction "18_18") (pintype "passive"))
    )
    (net (code "145") (name "unconnected-(J4-Pad19)") (class "Default")
      (node (ref "J4") (pin "19") (pinfunction "19_19") (pintype "passive"))
    )
    (net (code "146") (name "unconnected-(J4-Pad20)") (class "Default")
      (node (ref "J4") (pin "20") (pinfunction "20_20") (pintype "passive"))
    )
    (net (code "147") (name "unconnected-(PS1-VADJ-Pad12)") (class "Default")
      (node (ref "PS1") (pin "12") (pinfunction "VADJ_12") (pintype "passive"))
    )
    (net (code "148") (name "unconnected-(PS2-VADJ-Pad12)") (class "Default")
      (node (ref "PS2") (pin "12") (pinfunction "VADJ_12") (pintype "passive"))
    )
  )
)
